# Cheeta_Controller.net
KiCad netlist of a schematic drawn in Altium Designer
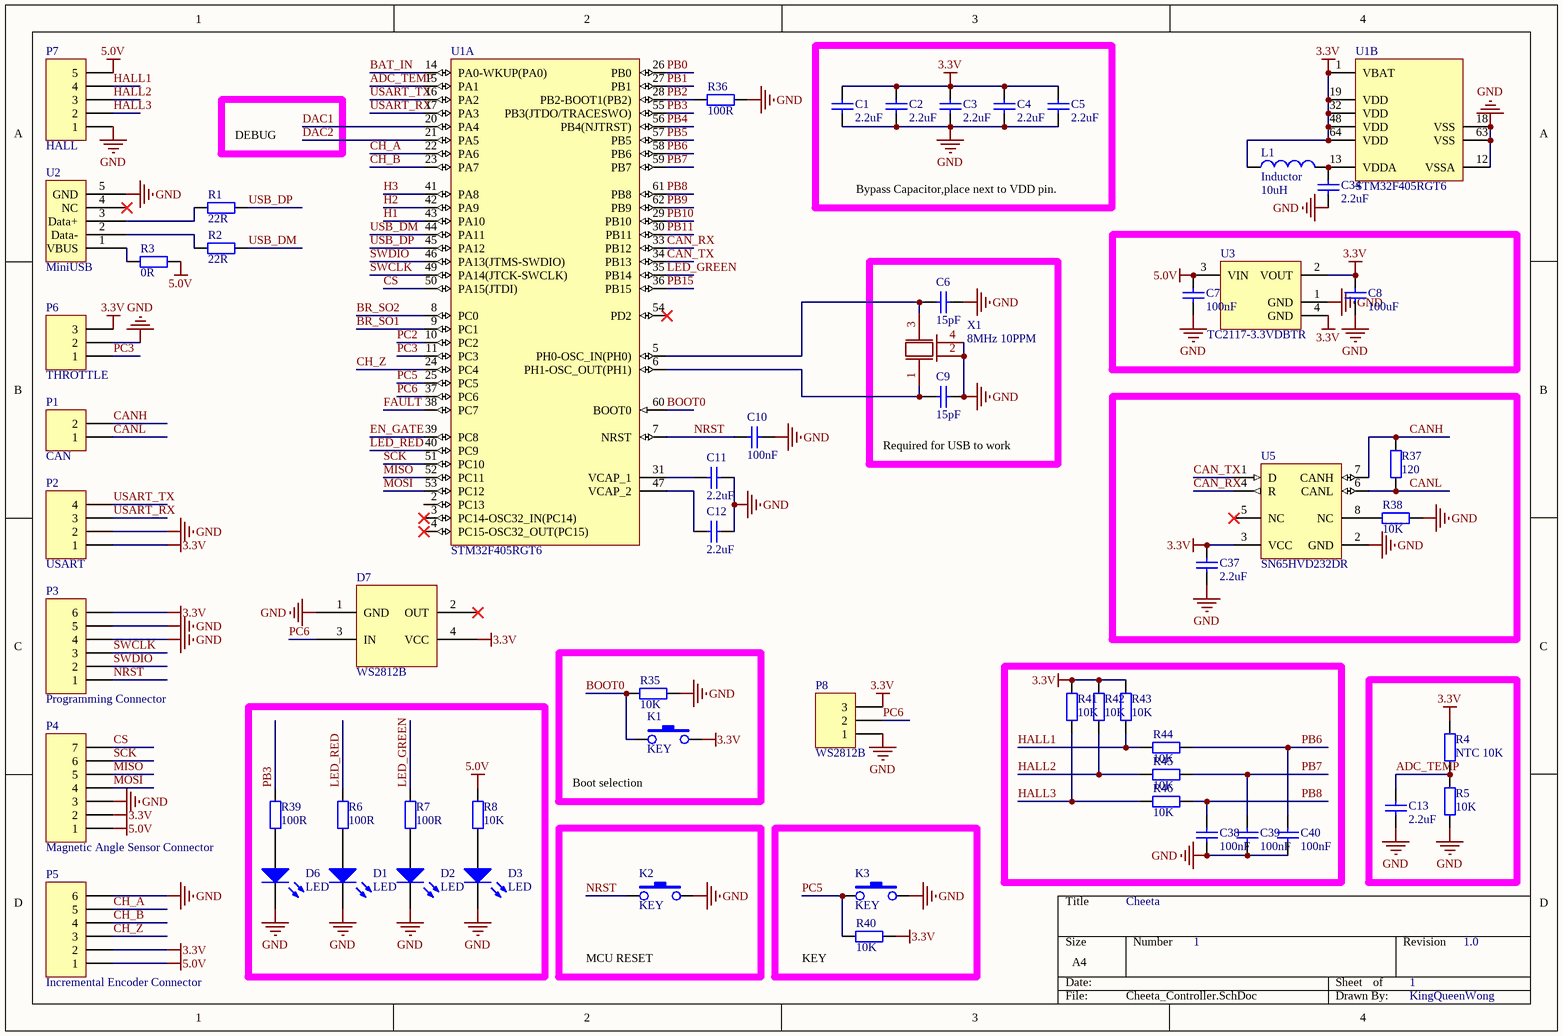
[diagram p0: Cheeta_Controller.SchDoc]

(export (version "E")
  (design (tool "Eeschema 10.0.6"))
  (components
    (comp (ref "C1")
      (value "2.2uF")
      (footprint "0603C")
      (description "Capacitor")
      (fields (field (name "Comment") "Cap") (field (name "PUBLISHER") "Altium Limited"))
      (libsource (lib "Miscellaneous Devices") (part "Cap"))
    )
    (comp (ref "C2")
      (value "2.2uF")
      (footprint "0603C")
      (description "Capacitor")
      (fields (field (name "Comment") "Cap") (field (name "PUBLISHER") "Altium Limited"))
      (libsource (lib "Miscellaneous Devices") (part "Cap"))
    )
    (comp (ref "C3")
      (value "2.2uF")
      (footprint "0603C")
      (description "Capacitor")
      (fields (field (name "Comment") "Cap") (field (name "PUBLISHER") "Altium Limited"))
      (libsource (lib "Miscellaneous Devices") (part "Cap"))
    )
    (comp (ref "C4")
      (value "2.2uF")
      (footprint "0603C")
      (description "Capacitor")
      (fields (field (name "Comment") "Cap") (field (name "PUBLISHER") "Altium Limited"))
      (libsource (lib "Miscellaneous Devices") (part "Cap"))
    )
    (comp (ref "C5")
      (value "2.2uF")
      (footprint "0603C")
      (description "Capacitor")
      (fields (field (name "Comment") "Cap") (field (name "PUBLISHER") "Altium Limited"))
      (libsource (lib "Miscellaneous Devices") (part "Cap"))
    )
    (comp (ref "C6")
      (value "15pF")
      (footprint "0603C")
      (description "Capacitor")
      (fields (field (name "Comment") "Cap") (field (name "PUBLISHER") "Altium Limited"))
      (libsource (lib "Miscellaneous Devices") (part "Cap"))
    )
    (comp (ref "C7")
      (value "100nF")
      (footprint "0603C")
      (description "Capacitor")
      (fields (field (name "Comment") "Cap") (field (name "PUBLISHER") "Altium Limited"))
      (libsource (lib "Miscellaneous Devices") (part "Cap"))
    )
    (comp (ref "C8")
      (value "100uF")
      (footprint "C1210")
      (description "Capacitor")
      (fields (field (name "Comment") "Cap") (field (name "PUBLISHER") "Altium Limited"))
      (libsource (lib "Miscellaneous Devices") (part "Cap"))
    )
    (comp (ref "C9")
      (value "15pF")
      (footprint "0603C")
      (description "Capacitor")
      (fields (field (name "Comment") "Cap") (field (name "PUBLISHER") "Altium Limited"))
      (libsource (lib "Miscellaneous Devices") (part "Cap"))
    )
    (comp (ref "C10")
      (value "100nF")
      (footprint "0603C")
      (description "Capacitor")
      (fields (field (name "Comment") "Cap") (field (name "PUBLISHER") "Altium Limited"))
      (libsource (lib "Miscellaneous Devices") (part "Cap"))
    )
    (comp (ref "C11")
      (value "2.2uF")
      (footprint "0603C")
      (description "Capacitor")
      (fields (field (name "Comment") "Cap") (field (name "PUBLISHER") "Altium Limited"))
      (libsource (lib "Miscellaneous Devices") (part "Cap"))
    )
    (comp (ref "C12")
      (value "2.2uF")
      (footprint "0603C")
      (description "Capacitor")
      (fields (field (name "Comment") "Cap") (field (name "PUBLISHER") "Altium Limited"))
      (libsource (lib "Miscellaneous Devices") (part "Cap"))
    )
    (comp (ref "C13")
      (value "2.2uF")
      (footprint "0603C")
      (description "Capacitor")
      (fields (field (name "Comment") "Cap") (field (name "PUBLISHER") "Altium Limited"))
      (libsource (lib "Miscellaneous Devices") (part "Cap"))
    )
    (comp (ref "C34")
      (value "2.2uF")
      (footprint "0603C")
      (description "Capacitor")
      (fields (field (name "Comment") "Cap") (field (name "PUBLISHER") "Altium Limited"))
      (libsource (lib "Miscellaneous Devices") (part "Cap"))
    )
    (comp (ref "C37")
      (value "2.2uF")
      (footprint "0603C")
      (description "Capacitor")
      (fields (field (name "Comment") "Cap") (field (name "PUBLISHER") "Altium Limited"))
      (libsource (lib "Miscellaneous Devices") (part "Cap"))
    )
    (comp (ref "C38")
      (value "100nF")
      (footprint "0603C")
      (description "Capacitor")
      (fields (field (name "Comment") "Cap") (field (name "PUBLISHER") "Altium Limited"))
      (libsource (lib "Miscellaneous Devices") (part "Cap"))
    )
    (comp (ref "C39")
      (value "100nF")
      (footprint "0603C")
      (description "Capacitor")
      (fields (field (name "Comment") "Cap") (field (name "PUBLISHER") "Altium Limited"))
      (libsource (lib "Miscellaneous Devices") (part "Cap"))
    )
    (comp (ref "C40")
      (value "100nF")
      (footprint "0603C")
      (description "Capacitor")
      (fields (field (name "Comment") "Cap") (field (name "PUBLISHER") "Altium Limited"))
      (libsource (lib "Miscellaneous Devices") (part "Cap"))
    )
    (comp (ref "D1")
      (value "LED")
      (footprint "0603D")
      (description "Typical INFRARED GaAs LED")
      (fields (field (name "PUBLISHER") "Altium Limited"))
      (libsource (lib "Miscellaneous Devices") (part "LED0"))
    )
    (comp (ref "D2")
      (value "LED")
      (footprint "0603D")
      (description "Typical INFRARED GaAs LED")
      (fields (field (name "PUBLISHER") "Altium Limited"))
      (libsource (lib "Miscellaneous Devices") (part "LED0"))
    )
    (comp (ref "D3")
      (value "LED")
      (footprint "0603D")
      (description "Typical INFRARED GaAs LED")
      (fields (field (name "PUBLISHER") "Altium Limited"))
      (libsource (lib "Miscellaneous Devices") (part "LED0"))
    )
    (comp (ref "D6")
      (value "LED")
      (footprint "0603D")
      (description "Typical INFRARED GaAs LED")
      (fields (field (name "PUBLISHER") "Altium Limited"))
      (libsource (lib "Miscellaneous Devices") (part "LED0"))
    )
    (comp (ref "D7")
      (value "WS2812B")
      (footprint "WS2812B")
      (libsource (lib "FreshPersimmon_Schematic") (part "WS2812B"))
    )
    (comp (ref "K1") (value "KEY") (footprint "KEY3*4") (libsource (lib "Schlib") (part "KEY")))
    (comp (ref "K2") (value "KEY") (footprint "KEY3*4") (libsource (lib "Schlib") (part "KEY")))
    (comp (ref "K3") (value "KEY") (footprint "KEY3*4") (libsource (lib "Schlib") (part "KEY")))
    (comp (ref "L1")
      (value "Inductor")
      (footprint "0603C")
      (fields (field (name "ALTIUM_VALUE") "10uH") (field (name "PUBLISHER") "Altium Limited"))
      (libsource (lib "Miscellaneous Devices") (part "Inductor"))
    )
    (comp (ref "P1")
      (value "CAN")
      (footprint "SH1.0_2P")
      (description "Header, 2-Pin")
      (fields (field (name "PUBLISHER") "Altium Limited"))
      (libsource (lib "Miscellaneous Connectors") (part "Header 2"))
    )
    (comp (ref "P2")
      (value "USART")
      (footprint "SH1.0_4P")
      (description "Header, 4-Pin")
      (fields (field (name "PUBLISHER") "Altium Limited"))
      (libsource (lib "Miscellaneous Connectors") (part "MHDR1X4"))
    )
    (comp (ref "P3")
      (value "Programming Connector")
      (footprint "SH1.0_6P")
      (description "Header, 6-Pin")
      (fields (field (name "PUBLISHER") "Altium Limited"))
      (libsource (lib "Miscellaneous Connectors") (part "MHDR1X6"))
    )
    (comp (ref "P4")
      (value "Magnetic Angle Sensor Connector")
      (footprint "SH1.0_7P")
      (description "Header, 7-Pin")
      (fields (field (name "PUBLISHER") "Altium Limited"))
      (libsource (lib "Miscellaneous Connectors") (part "MHDR1X7"))
    )
    (comp (ref "P5")
      (value "Incremental Encoder Connector")
      (footprint "SH1.0_6P")
      (description "Header, 6-Pin")
      (fields (field (name "PUBLISHER") "Altium Limited"))
      (libsource (lib "Miscellaneous Connectors") (part "MHDR1X6"))
    )
    (comp (ref "P6")
      (value "THROTTLE")
      (footprint "SH1.0_3P")
      (description "Header, 3-Pin")
      (fields (field (name "PUBLISHER") "Altium Limited"))
      (libsource (lib "Miscellaneous Connectors") (part "Header 3"))
    )
    (comp (ref "P7")
      (value "HALL")
      (footprint "SH1.0_5P")
      (description "Header, 5-Pin")
      (fields (field (name "PUBLISHER") "Altium Limited"))
      (libsource (lib "Miscellaneous Connectors") (part "Header 5"))
    )
    (comp (ref "P8")
      (value "WS2812B")
      (footprint "SH1.0_3P")
      (description "Header, 3-Pin")
      (fields (field (name "PUBLISHER") "Altium Limited"))
      (libsource (lib "Miscellaneous Connectors") (part "Header 3"))
    )
    (comp (ref "R1")
      (value "22R")
      (footprint "0603R")
      (description "Resistor")
      (fields (field (name "Comment") "Res2") (field (name "PUBLISHER") "Altium Limited"))
      (libsource (lib "") (part "Res2_2"))
    )
    (comp (ref "R2")
      (value "22R")
      (footprint "0603R")
      (description "Resistor")
      (fields (field (name "Comment") "Res2") (field (name "PUBLISHER") "Altium Limited"))
      (libsource (lib "") (part "Res2_2"))
    )
    (comp (ref "R3")
      (value "0R")
      (footprint "0603R")
      (description "Resistor")
      (fields (field (name "Comment") "Res2") (field (name "PUBLISHER") "Altium Limited"))
      (libsource (lib "") (part "Res2_2"))
    )
    (comp (ref "R4")
      (value "NTC 10K")
      (footprint "0603R")
      (description "Resistor")
      (fields (field (name "Comment") "Res2") (field (name "PUBLISHER") "Altium Limited"))
      (libsource (lib "Miscellaneous Devices") (part "Res2"))
    )
    (comp (ref "R5")
      (value "10K")
      (footprint "0603R")
      (description "Resistor")
      (fields (field (name "Comment") "Res2") (field (name "PUBLISHER") "Altium Limited"))
      (libsource (lib "Miscellaneous Devices") (part "Res2"))
    )
    (comp (ref "R6")
      (value "100R")
      (footprint "0603R")
      (description "Resistor")
      (fields (field (name "Comment") "Res2") (field (name "PUBLISHER") "Altium Limited"))
      (libsource (lib "") (part "Res2_1"))
    )
    (comp (ref "R7")
      (value "100R")
      (footprint "0603R")
      (description "Resistor")
      (fields (field (name "Comment") "Res2") (field (name "PUBLISHER") "Altium Limited"))
      (libsource (lib "") (part "Res2_1"))
    )
    (comp (ref "R8")
      (value "10K")
      (footprint "0603R")
      (description "Resistor")
      (fields (field (name "Comment") "Res2") (field (name "PUBLISHER") "Altium Limited"))
      (libsource (lib "") (part "Res2_1"))
    )
    (comp (ref "R35")
      (value "10K")
      (footprint "0603R")
      (description "Resistor")
      (fields (field (name "Comment") "Res2") (field (name "PUBLISHER") "Altium Limited"))
      (libsource (lib "") (part "Res2_2"))
    )
    (comp (ref "R36")
      (value "100R")
      (footprint "0603R")
      (description "Resistor")
      (fields (field (name "Comment") "Res2") (field (name "PUBLISHER") "Altium Limited"))
      (libsource (lib "") (part "Res2_2"))
    )
    (comp (ref "R37")
      (value "120")
      (footprint "0603R")
      (description "Resistor")
      (fields (field (name "Comment") "Res2") (field (name "PUBLISHER") "Altium Limited"))
      (libsource (lib "") (part "Res2_1"))
    )
    (comp (ref "R38")
      (value "10K")
      (footprint "0603R")
      (description "Resistor")
      (fields (field (name "Comment") "Res2") (field (name "PUBLISHER") "Altium Limited"))
      (libsource (lib "") (part "Res2_3"))
    )
    (comp (ref "R39")
      (value "100R")
      (footprint "0603R")
      (description "Resistor")
      (fields (field (name "Comment") "Res2") (field (name "PUBLISHER") "Altium Limited"))
      (libsource (lib "") (part "Res2_1"))
    )
    (comp (ref "R40")
      (value "10K")
      (footprint "0603R")
      (description "Resistor")
      (fields (field (name "Comment") "Res2") (field (name "PUBLISHER") "Altium Limited"))
      (libsource (lib "") (part "Res2_2"))
    )
    (comp (ref "R41")
      (value "10K")
      (footprint "0603R")
      (description "Resistor")
      (fields (field (name "Comment") "Res2") (field (name "PUBLISHER") "Altium Limited"))
      (libsource (lib "") (part "Res2_1"))
    )
    (comp (ref "R42")
      (value "10K")
      (footprint "0603R")
      (description "Resistor")
      (fields (field (name "Comment") "Res2") (field (name "PUBLISHER") "Altium Limited"))
      (libsource (lib "") (part "Res2_1"))
    )
    (comp (ref "R43")
      (value "10K")
      (footprint "0603R")
      (description "Resistor")
      (fields (field (name "Comment") "Res2") (field (name "PUBLISHER") "Altium Limited"))
      (libsource (lib "") (part "Res2_1"))
    )
    (comp (ref "R44")
      (value "10K")
      (footprint "0603R")
      (description "Resistor")
      (fields (field (name "Comment") "Res2") (field (name "PUBLISHER") "Altium Limited"))
      (libsource (lib "") (part "Res2_2"))
    )
    (comp (ref "R45")
      (value "10K")
      (footprint "0603R")
      (description "Resistor")
      (fields (field (name "Comment") "Res2") (field (name "PUBLISHER") "Altium Limited"))
      (libsource (lib "") (part "Res2_2"))
    )
    (comp (ref "R46")
      (value "10K")
      (footprint "0603R")
      (description "Resistor")
      (fields (field (name "Comment") "Res2") (field (name "PUBLISHER") "Altium Limited"))
      (libsource (lib "") (part "Res2_2"))
    )
    (comp (ref "U1")
      (value "STM32F405RGT6")
      (footprint "STM-LQFP64_N")
      (fields (field (name "MANUFACTURER") "STMicroelectronics"))
      (libsource (lib "STMicroelectronics STM32 F4") (part "STM32F405RGT6"))
    )
    (comp (ref "U2")
      (value "MiniUSB")
      (footprint "MINI-USB")
      (libsource (lib "FreshPersimmon_Schematic") (part "MiniUSB"))
    )
    (comp (ref "U3")
      (value "TC2117-3.3VDBTR")
      (footprint "SOT-223-DB3_N")
      (description "800 mA Fixed Low Dropout Positive Regulator, 3-Pin SOT-223, Extended Temperature, Tape and Reel")
      (fields (field (name "MANUFACTURER") "Microchip"))
      (libsource (lib "Microchip Power Management Line Regulator") (part "TC2117-3.3VDBTR"))
    )
    (comp (ref "U5")
      (value "SN65HVD232DR")
      (footprint "D8_L")
      (description "3.3 V Can Transceiver, 17 mA, -40 to 85 degC, 8-pin SOIC (D), Green (RoHS & no Sb/Br)")
      (fields (field (name "MANUFACTURER") "Texas Instruments"))
      (libsource (lib "Texas Instruments Interface CAN") (part "SN65HVD232DR"))
    )
    (comp (ref "X1")
      (value "8MHz 10PPM")
      (footprint "ABM3B")
      (description "Crystal Oscillator")
      (libsource (lib "CKM") (part "TZ1430A"))
    )
  )
  (nets
    (net (code "1") (name "/ADC_TEMP") (class "Default")
      (node (ref "C13") (pin "2") (pinfunction "2_2") (pintype "passive"))
      (node (ref "R4") (pin "2") (pinfunction "2_2") (pintype "passive"))
      (node (ref "R5") (pin "1") (pinfunction "1_1") (pintype "passive"))
      (node (ref "U1") (pin "15") (pinfunction "PA1_15") (pintype "bidirectional"))
    )
    (net (code "2") (name "/BAT_IN") (class "Default")
      (node (ref "U1") (pin "14") (pinfunction "PA0-WKUP(PA0)_14") (pintype "bidirectional"))
    )
    (net (code "3") (name "/BOOT0") (class "Default")
      (node (ref "K1") (pin "1") (pinfunction "1_1") (pintype "passive"))
      (node (ref "R35") (pin "2") (pinfunction "2_2") (pintype "passive"))
      (node (ref "U1") (pin "60") (pinfunction "BOOT0_60") (pintype "input"))
    )
    (net (code "4") (name "/BR_SO1") (class "Default")
      (node (ref "U1") (pin "9") (pinfunction "PC1_9") (pintype "bidirectional"))
    )
    (net (code "5") (name "/BR_SO2") (class "Default")
      (node (ref "U1") (pin "8") (pinfunction "PC0_8") (pintype "bidirectional"))
    )
    (net (code "6") (name "/CANH") (class "Default")
      (node (ref "P1") (pin "2") (pinfunction "2_2") (pintype "passive"))
      (node (ref "R37") (pin "2") (pinfunction "2_2") (pintype "passive"))
      (node (ref "U5") (pin "7") (pinfunction "CANH_7") (pintype "bidirectional"))
    )
    (net (code "7") (name "/CANL") (class "Default")
      (node (ref "P1") (pin "1") (pinfunction "1_1") (pintype "passive"))
      (node (ref "R37") (pin "1") (pinfunction "1_1") (pintype "passive"))
      (node (ref "U5") (pin "6") (pinfunction "CANL_6") (pintype "bidirectional"))
    )
    (net (code "8") (name "/CAN_RX") (class "Default")
      (node (ref "U1") (pin "33") (pinfunction "PB12_33") (pintype "bidirectional"))
      (node (ref "U5") (pin "4") (pinfunction "R_4") (pintype "output"))
    )
    (net (code "9") (name "/CAN_TX") (class "Default")
      (node (ref "U1") (pin "34") (pinfunction "PB13_34") (pintype "bidirectional"))
      (node (ref "U5") (pin "1") (pinfunction "D_1") (pintype "input"))
    )
    (net (code "10") (name "/CH_A") (class "Default")
      (node (ref "P5") (pin "5") (pinfunction "5_5") (pintype "passive"))
      (node (ref "U1") (pin "22") (pinfunction "PA6_22") (pintype "bidirectional"))
    )
    (net (code "11") (name "/CH_B") (class "Default")
      (node (ref "P5") (pin "4") (pinfunction "4_4") (pintype "passive"))
      (node (ref "U1") (pin "23") (pinfunction "PA7_23") (pintype "bidirectional"))
    )
    (net (code "12") (name "/CH_Z") (class "Default")
      (node (ref "P5") (pin "3") (pinfunction "3_3") (pintype "passive"))
      (node (ref "U1") (pin "24") (pinfunction "PC4_24") (pintype "bidirectional"))
    )
    (net (code "13") (name "/CS") (class "Default")
      (node (ref "P4") (pin "7") (pinfunction "7_7") (pintype "passive"))
      (node (ref "U1") (pin "50") (pinfunction "PA15(JTDI)_50") (pintype "bidirectional"))
    )
    (net (code "14") (name "/DAC1") (class "Default")
      (node (ref "U1") (pin "20") (pinfunction "PA4_20") (pintype "bidirectional"))
    )
    (net (code "15") (name "/DAC2") (class "Default")
      (node (ref "U1") (pin "21") (pinfunction "PA5_21") (pintype "bidirectional"))
    )
    (net (code "16") (name "/EN_GATE") (class "Default")
      (node (ref "U1") (pin "39") (pinfunction "PC8_39") (pintype "bidirectional"))
    )
    (net (code "17") (name "/FAULT") (class "Default")
      (node (ref "U1") (pin "38") (pinfunction "PC7_38") (pintype "bidirectional"))
    )
    (net (code "18") (name "/H1") (class "Default")
      (node (ref "U1") (pin "43") (pinfunction "PA10_43") (pintype "bidirectional"))
    )
    (net (code "19") (name "/H2") (class "Default")
      (node (ref "U1") (pin "42") (pinfunction "PA9_42") (pintype "bidirectional"))
    )
    (net (code "20") (name "/H3") (class "Default")
      (node (ref "U1") (pin "41") (pinfunction "PA8_41") (pintype "bidirectional"))
    )
    (net (code "21") (name "/HALL1") (class "Default")
      (node (ref "P7") (pin "4") (pinfunction "4_4") (pintype "passive"))
      (node (ref "R43") (pin "1") (pinfunction "1_1") (pintype "passive"))
      (node (ref "R44") (pin "2") (pinfunction "2_2") (pintype "passive"))
    )
    (net (code "22") (name "/HALL2") (class "Default")
      (node (ref "P7") (pin "3") (pinfunction "3_3") (pintype "passive"))
      (node (ref "R42") (pin "1") (pinfunction "1_1") (pintype "passive"))
      (node (ref "R45") (pin "2") (pinfunction "2_2") (pintype "passive"))
    )
    (net (code "23") (name "/HALL3") (class "Default")
      (node (ref "P7") (pin "2") (pinfunction "2_2") (pintype "passive"))
      (node (ref "R41") (pin "1") (pinfunction "1_1") (pintype "passive"))
      (node (ref "R46") (pin "2") (pinfunction "2_2") (pintype "passive"))
    )
    (net (code "24") (name "/LED_GREEN") (class "Default")
      (node (ref "R7") (pin "2") (pinfunction "2_2") (pintype "passive"))
      (node (ref "U1") (pin "35") (pinfunction "PB14_35") (pintype "bidirectional"))
    )
    (net (code "25") (name "/LED_RED") (class "Default")
      (node (ref "R6") (pin "2") (pinfunction "2_2") (pintype "passive"))
      (node (ref "U1") (pin "40") (pinfunction "PC9_40") (pintype "bidirectional"))
    )
    (net (code "26") (name "/MISO") (class "Default")
      (node (ref "P4") (pin "5") (pinfunction "5_5") (pintype "passive"))
      (node (ref "U1") (pin "52") (pinfunction "PC11_52") (pintype "bidirectional"))
    )
    (net (code "27") (name "/MOSI") (class "Default")
      (node (ref "P4") (pin "4") (pinfunction "4_4") (pintype "passive"))
      (node (ref "U1") (pin "53") (pinfunction "PC12_53") (pintype "bidirectional"))
    )
    (net (code "28") (name "/NRST") (class "Default")
      (node (ref "C10") (pin "1") (pinfunction "1_1") (pintype "passive"))
      (node (ref "K2") (pin "1") (pinfunction "1_1") (pintype "passive"))
      (node (ref "P3") (pin "1") (pinfunction "1_1") (pintype "passive"))
      (node (ref "U1") (pin "7") (pinfunction "NRST_7") (pintype "bidirectional"))
    )
    (net (code "29") (name "/PB0") (class "Default")
      (node (ref "U1") (pin "26") (pinfunction "PB0_26") (pintype "bidirectional"))
    )
    (net (code "30") (name "/PB1") (class "Default")
      (node (ref "U1") (pin "27") (pinfunction "PB1_27") (pintype "bidirectional"))
    )
    (net (code "31") (name "/PB2") (class "Default")
      (node (ref "R36") (pin "2") (pinfunction "2_2") (pintype "passive"))
      (node (ref "U1") (pin "28") (pinfunction "PB2-BOOT1(PB2)_28") (pintype "bidirectional"))
    )
    (net (code "32") (name "/PB3") (class "Default")
      (node (ref "R39") (pin "2") (pinfunction "2_2") (pintype "passive"))
      (node (ref "U1") (pin "55") (pinfunction "PB3(JTDO/TRACESWO)_55") (pintype "bidirectional"))
    )
    (net (code "33") (name "/PB4") (class "Default")
      (node (ref "U1") (pin "56") (pinfunction "PB4(NJTRST)_56") (pintype "bidirectional"))
    )
    (net (code "34") (name "/PB5") (class "Default")
      (node (ref "U1") (pin "57") (pinfunction "PB5_57") (pintype "bidirectional"))
    )
    (net (code "35") (name "/PB6") (class "Default")
      (node (ref "C40") (pin "2") (pinfunction "2_2") (pintype "passive"))
      (node (ref "R44") (pin "1") (pinfunction "1_1") (pintype "passive"))
      (node (ref "U1") (pin "58") (pinfunction "PB6_58") (pintype "bidirectional"))
    )
    (net (code "36") (name "/PB7") (class "Default")
      (node (ref "C39") (pin "2") (pinfunction "2_2") (pintype "passive"))
      (node (ref "R45") (pin "1") (pinfunction "1_1") (pintype "passive"))
      (node (ref "U1") (pin "59") (pinfunction "PB7_59") (pintype "bidirectional"))
    )
    (net (code "37") (name "/PB8") (class "Default")
      (node (ref "C38") (pin "2") (pinfunction "2_2") (pintype "passive"))
      (node (ref "R46") (pin "1") (pinfunction "1_1") (pintype "passive"))
      (node (ref "U1") (pin "61") (pinfunction "PB8_61") (pintype "bidirectional"))
    )
    (net (code "38") (name "/PB9") (class "Default")
      (node (ref "U1") (pin "62") (pinfunction "PB9_62") (pintype "bidirectional"))
    )
    (net (code "39") (name "/PB10") (class "Default")
      (node (ref "U1") (pin "29") (pinfunction "PB10_29") (pintype "bidirectional"))
    )
    (net (code "40") (name "/PB11") (class "Default")
      (node (ref "U1") (pin "30") (pinfunction "PB11_30") (pintype "bidirectional"))
    )
    (net (code "41") (name "/PB15") (class "Default")
      (node (ref "U1") (pin "36") (pinfunction "PB15_36") (pintype "bidirectional"))
    )
    (net (code "42") (name "/PC2") (class "Default")
      (node (ref "U1") (pin "10") (pinfunction "PC2_10") (pintype "bidirectional"))
    )
    (net (code "43") (name "/PC3") (class "Default")
      (node (ref "P6") (pin "1") (pinfunction "1_1") (pintype "passive"))
      (node (ref "U1") (pin "11") (pinfunction "PC3_11") (pintype "bidirectional"))
    )
    (net (code "44") (name "/PC5") (class "Default")
      (node (ref "K3") (pin "1") (pinfunction "1_1") (pintype "passive"))
      (node (ref "R40") (pin "2") (pinfunction "2_2") (pintype "passive"))
      (node (ref "U1") (pin "25") (pinfunction "PC5_25") (pintype "bidirectional"))
    )
    (net (code "45") (name "/PC6") (class "Default")
      (node (ref "D7") (pin "3") (pinfunction "IN_3") (pintype "passive"))
      (node (ref "P8") (pin "2") (pinfunction "2_2") (pintype "passive"))
      (node (ref "U1") (pin "37") (pinfunction "PC6_37") (pintype "bidirectional"))
    )
    (net (code "46") (name "/SCK") (class "Default")
      (node (ref "P4") (pin "6") (pinfunction "6_6") (pintype "passive"))
      (node (ref "U1") (pin "51") (pinfunction "PC10_51") (pintype "bidirectional"))
    )
    (net (code "47") (name "/SWCLK") (class "Default")
      (node (ref "P3") (pin "3") (pinfunction "3_3") (pintype "passive"))
      (node (ref "U1") (pin "49") (pinfunction "PA14(JTCK-SWCLK)_49") (pintype "bidirectional"))
    )
    (net (code "48") (name "/SWDIO") (class "Default")
      (node (ref "P3") (pin "2") (pinfunction "2_2") (pintype "passive"))
      (node (ref "U1") (pin "46") (pinfunction "PA13(JTMS-SWDIO)_46") (pintype "bidirectional"))
    )
    (net (code "49") (name "/USART_RX") (class "Default")
      (node (ref "P2") (pin "3") (pinfunction "3_3") (pintype "passive"))
      (node (ref "U1") (pin "17") (pinfunction "PA3_17") (pintype "bidirectional"))
    )
    (net (code "50") (name "/USART_TX") (class "Default")
      (node (ref "P2") (pin "4") (pinfunction "4_4") (pintype "passive"))
      (node (ref "U1") (pin "16") (pinfunction "PA2_16") (pintype "bidirectional"))
    )
    (net (code "51") (name "/USB_DM") (class "Default")
      (node (ref "R2") (pin "1") (pinfunction "1_1") (pintype "passive"))
      (node (ref "U1") (pin "44") (pinfunction "PA11_44") (pintype "bidirectional"))
    )
    (net (code "52") (name "/USB_DP") (class "Default")
      (node (ref "R1") (pin "1") (pinfunction "1_1") (pintype "passive"))
      (node (ref "U1") (pin "45") (pinfunction "PA12_45") (pintype "bidirectional"))
    )
    (net (code "53") (name "3.3V") (class "Default")
      (node (ref "C1") (pin "2") (pinfunction "2_2") (pintype "passive"))
      (node (ref "C2") (pin "2") (pinfunction "2_2") (pintype "passive"))
      (node (ref "C3") (pin "2") (pinfunction "2_2") (pintype "passive"))
      (node (ref "C37") (pin "1") (pinfunction "1_1") (pintype "passive"))
      (node (ref "C4") (pin "2") (pinfunction "2_2") (pintype "passive"))
      (node (ref "C5") (pin "2") (pinfunction "2_2") (pintype "passive"))
      (node (ref "C8") (pin "2") (pinfunction "2_2") (pintype "passive"))
      (node (ref "D7") (pin "4") (pinfunction "VCC_4") (pintype "passive"))
      (node (ref "K1") (pin "2") (pinfunction "2_2") (pintype "passive"))
      (node (ref "L1") (pin "1") (pinfunction "1_1") (pintype "passive"))
      (node (ref "P2") (pin "1") (pinfunction "1_1") (pintype "passive"))
      (node (ref "P3") (pin "6") (pinfunction "6_6") (pintype "passive"))
      (node (ref "P4") (pin "2") (pinfunction "2_2") (pintype "passive"))
      (node (ref "P5") (pin "2") (pinfunction "2_2") (pintype "passive"))
      (node (ref "P6") (pin "3") (pinfunction "3_3") (pintype "passive"))
      (node (ref "P8") (pin "3") (pinfunction "3_3") (pintype "passive"))
      (node (ref "R4") (pin "1") (pinfunction "1_1") (pintype "passive"))
      (node (ref "R40") (pin "1") (pinfunction "1_1") (pintype "passive"))
      (node (ref "R41") (pin "2") (pinfunction "2_2") (pintype "passive"))
      (node (ref "R42") (pin "2") (pinfunction "2_2") (pintype "passive"))
      (node (ref "R43") (pin "2") (pinfunction "2_2") (pintype "passive"))
      (node (ref "U1") (pin "1") (pinfunction "VBAT_1") (pintype "power_in"))
      (node (ref "U1") (pin "19") (pinfunction "VDD_19") (pintype "power_in"))
      (node (ref "U1") (pin "32") (pinfunction "VDD_32") (pintype "power_in"))
      (node (ref "U1") (pin "48") (pinfunction "VDD_48") (pintype "power_in"))
      (node (ref "U1") (pin "64") (pinfunction "VDD_64") (pintype "power_in"))
      (node (ref "U3") (pin "2") (pinfunction "VOUT_2") (pintype "power_in"))
      (node (ref "U3") (pin "4") (pinfunction "GND_4") (pintype "power_in"))
      (node (ref "U5") (pin "3") (pinfunction "VCC_3") (pintype "power_in"))
    )
    (net (code "54") (name "5.0V") (class "Default")
      (node (ref "C7") (pin "2") (pinfunction "2_2") (pintype "passive"))
      (node (ref "P4") (pin "1") (pinfunction "1_1") (pintype "passive"))
      (node (ref "P5") (pin "1") (pinfunction "1_1") (pintype "passive"))
      (node (ref "P7") (pin "5") (pinfunction "5_5") (pintype "passive"))
      (node (ref "R3") (pin "1") (pinfunction "1_1") (pintype "passive"))
      (node (ref "R8") (pin "2") (pinfunction "2_2") (pintype "passive"))
      (node (ref "U3") (pin "3") (pinfunction "VIN_3") (pintype "power_in"))
    )
    (net (code "55") (name "GND") (class "Default")
      (node (ref "C1") (pin "1") (pinfunction "1_1") (pintype "passive"))
      (node (ref "C10") (pin "2") (pinfunction "2_2") (pintype "passive"))
      (node (ref "C11") (pin "2") (pinfunction "2_2") (pintype "passive"))
      (node (ref "C12") (pin "2") (pinfunction "2_2") (pintype "passive"))
      (node (ref "C13") (pin "1") (pinfunction "1_1") (pintype "passive"))
      (node (ref "C2") (pin "1") (pinfunction "1_1") (pintype "passive"))
      (node (ref "C3") (pin "1") (pinfunction "1_1") (pintype "passive"))
      (node (ref "C34") (pin "1") (pinfunction "1_1") (pintype "passive"))
      (node (ref "C37") (pin "2") (pinfunction "2_2") (pintype "passive"))
      (node (ref "C38") (pin "1") (pinfunction "1_1") (pintype "passive"))
      (node (ref "C39") (pin "1") (pinfunction "1_1") (pintype "passive"))
      (node (ref "C4") (pin "1") (pinfunction "1_1") (pintype "passive"))
      (node (ref "C40") (pin "1") (pinfunction "1_1") (pintype "passive"))
      (node (ref "C5") (pin "1") (pinfunction "1_1") (pintype "passive"))
      (node (ref "C6") (pin "2") (pinfunction "2_2") (pintype "passive"))
      (node (ref "C7") (pin "1") (pinfunction "1_1") (pintype "passive"))
      (node (ref "C8") (pin "1") (pinfunction "1_1") (pintype "passive"))
      (node (ref "C9") (pin "2") (pinfunction "2_2") (pintype "passive"))
      (node (ref "D1") (pin "2") (pinfunction "K_2") (pintype "passive"))
      (node (ref "D2") (pin "2") (pinfunction "K_2") (pintype "passive"))
      (node (ref "D3") (pin "2") (pinfunction "K_2") (pintype "passive"))
      (node (ref "D6") (pin "2") (pinfunction "K_2") (pintype "passive"))
      (node (ref "D7") (pin "1") (pinfunction "GND_1") (pintype "passive"))
      (node (ref "K2") (pin "2") (pinfunction "2_2") (pintype "passive"))
      (node (ref "K3") (pin "2") (pinfunction "2_2") (pintype "passive"))
      (node (ref "P2") (pin "2") (pinfunction "2_2") (pintype "passive"))
      (node (ref "P3") (pin "4") (pinfunction "4_4") (pintype "passive"))
      (node (ref "P3") (pin "5") (pinfunction "5_5") (pintype "passive"))
      (node (ref "P4") (pin "3") (pinfunction "3_3") (pintype "passive"))
      (node (ref "P5") (pin "6") (pinfunction "6_6") (pintype "passive"))
      (node (ref "P6") (pin "2") (pinfunction "2_2") (pintype "passive"))
      (node (ref "P7") (pin "1") (pinfunction "1_1") (pintype "passive"))
      (node (ref "P8") (pin "1") (pinfunction "1_1") (pintype "passive"))
      (node (ref "R35") (pin "1") (pinfunction "1_1") (pintype "passive"))
      (node (ref "R36") (pin "1") (pinfunction "1_1") (pintype "passive"))
      (node (ref "R38") (pin "2") (pinfunction "2_2") (pintype "passive"))
      (node (ref "R5") (pin "2") (pinfunction "2_2") (pintype "passive"))
      (node (ref "U1") (pin "12") (pinfunction "VSSA_12") (pintype "power_in"))
      (node (ref "U1") (pin "18") (pinfunction "VSS_18") (pintype "power_in"))
      (node (ref "U1") (pin "63") (pinfunction "VSS_63") (pintype "power_in"))
      (node (ref "U2") (pin "5") (pinfunction "GND_5") (pintype "passive"))
      (node (ref "U3") (pin "1") (pinfunction "GND_1") (pintype "power_in"))
      (node (ref "U5") (pin "2") (pinfunction "GND_2") (pintype "power_in"))
      (node (ref "X1") (pin "2") (pintype "passive"))
      (node (ref "X1") (pin "4") (pintype "passive"))
    )
    (net (code "56") (name "Net-(D1-A)") (class "Default")
      (node (ref "D1") (pin "1") (pinfunction "A_1") (pintype "passive"))
      (node (ref "R6") (pin "1") (pinfunction "1_1") (pintype "passive"))
    )
    (net (code "57") (name "Net-(D2-A)") (class "Default")
      (node (ref "D2") (pin "1") (pinfunction "A_1") (pintype "passive"))
      (node (ref "R7") (pin "1") (pinfunction "1_1") (pintype "passive"))
    )
    (net (code "58") (name "Net-(D3-A)") (class "Default")
      (node (ref "D3") (pin "1") (pinfunction "A_1") (pintype "passive"))
      (node (ref "R8") (pin "1") (pinfunction "1_1") (pintype "passive"))
    )
    (net (code "59") (name "Net-(D6-A)") (class "Default")
      (node (ref "D6") (pin "1") (pinfunction "A_1") (pintype "passive"))
      (node (ref "R39") (pin "1") (pinfunction "1_1") (pintype "passive"))
    )
    (net (code "60") (name "Net-(R38-Pad1)") (class "Default")
      (node (ref "R38") (pin "1") (pinfunction "1_1") (pintype "passive"))
      (node (ref "U5") (pin "8") (pinfunction "NC_8") (pintype "passive"))
    )
    (net (code "61") (name "Net-(U1A-PH0-OSC_IN(PH0))") (class "Default")
      (node (ref "C6") (pin "1") (pinfunction "1_1") (pintype "passive"))
      (node (ref "U1") (pin "5") (pinfunction "PH0-OSC_IN(PH0)_5") (pintype "bidirectional"))
      (node (ref "X1") (pin "3") (pintype "passive"))
    )
    (net (code "62") (name "Net-(U1A-PH1-OSC_OUT(PH1))") (class "Default")
      (node (ref "C9") (pin "1") (pinfunction "1_1") (pintype "passive"))
      (node (ref "U1") (pin "6") (pinfunction "PH1-OSC_OUT(PH1)_6") (pintype "bidirectional"))
      (node (ref "X1") (pin "1") (pintype "passive"))
    )
    (net (code "63") (name "Net-(U1A-VCAP_1)") (class "Default")
      (node (ref "C11") (pin "1") (pinfunction "1_1") (pintype "passive"))
      (node (ref "U1") (pin "31") (pinfunction "VCAP_1_31") (pintype "power_in"))
    )
    (net (code "64") (name "Net-(U1A-VCAP_2)") (class "Default")
      (node (ref "C12") (pin "1") (pinfunction "1_1") (pintype "passive"))
      (node (ref "U1") (pin "47") (pinfunction "VCAP_2_47") (pintype "power_in"))
    )
    (net (code "65") (name "Net-(U1B-VDDA)") (class "Default")
      (node (ref "C34") (pin "2") (pinfunction "2_2") (pintype "passive"))
      (node (ref "L1") (pin "2") (pinfunction "2_2") (pintype "passive"))
      (node (ref "U1") (pin "13") (pinfunction "VDDA_13") (pintype "power_in"))
    )
    (net (code "66") (name "Net-(U2-Data+)") (class "Default")
      (node (ref "R1") (pin "2") (pinfunction "2_2") (pintype "passive"))
      (node (ref "U2") (pin "3") (pinfunction "Data+_3") (pintype "passive"))
    )
    (net (code "67") (name "Net-(U2-Data-)") (class "Default")
      (node (ref "R2") (pin "2") (pinfunction "2_2") (pintype "passive"))
      (node (ref "U2") (pin "2") (pinfunction "Data-_2") (pintype "passive"))
    )
    (net (code "68") (name "Net-(U2-VBUS)") (class "Default")
      (node (ref "R3") (pin "2") (pinfunction "2_2") (pintype "passive"))
      (node (ref "U2") (pin "1") (pinfunction "VBUS_1") (pintype "passive"))
    )
    (net (code "69") (name "unconnected-(D7-OUT-Pad2)") (class "Default")
      (node (ref "D7") (pin "2") (pinfunction "OUT_2") (pintype "passive+no_connect"))
    )
    (net (code "70") (name "unconnected-(U1A-PC13-Pad2)") (class "Default")
      (node (ref "U1") (pin "2") (pinfunction "PC13_2") (pintype "bidirectional"))
    )
    (net (code "71") (name "unconnected-(U1A-PC14-OSC32_IN(PC14)-Pad3)") (class "Default")
      (node (ref "U1") (pin "3") (pinfunction "PC14-OSC32_IN(PC14)_3") (pintype "bidirectional+no_connect"))
    )
    (net (code "72") (name "unconnected-(U1A-PC15-OSC32_OUT(PC15)-Pad4)") (class "Default")
      (node (ref "U1") (pin "4") (pinfunction "PC15-OSC32_OUT(PC15)_4") (pintype "bidirectional+no_connect"))
    )
    (net (code "73") (name "unconnected-(U1A-PD2-Pad54)") (class "Default")
      (node (ref "U1") (pin "54") (pinfunction "PD2_54") (pintype "bidirectional+no_connect"))
    )
    (net (code "74") (name "unconnected-(U2-NC-Pad4)") (class "Default")
      (node (ref "U2") (pin "4") (pinfunction "NC_4") (pintype "passive+no_connect"))
    )
    (net (code "75") (name "unconnected-(U5-NC-Pad5)") (class "Default")
      (node (ref "U5") (pin "5") (pinfunction "NC_5") (pintype "passive+no_connect"))
    )
  )
)
